# High_Voltage_H-Bridge.net
KiCad netlist of a schematic drawn in Altium Designer
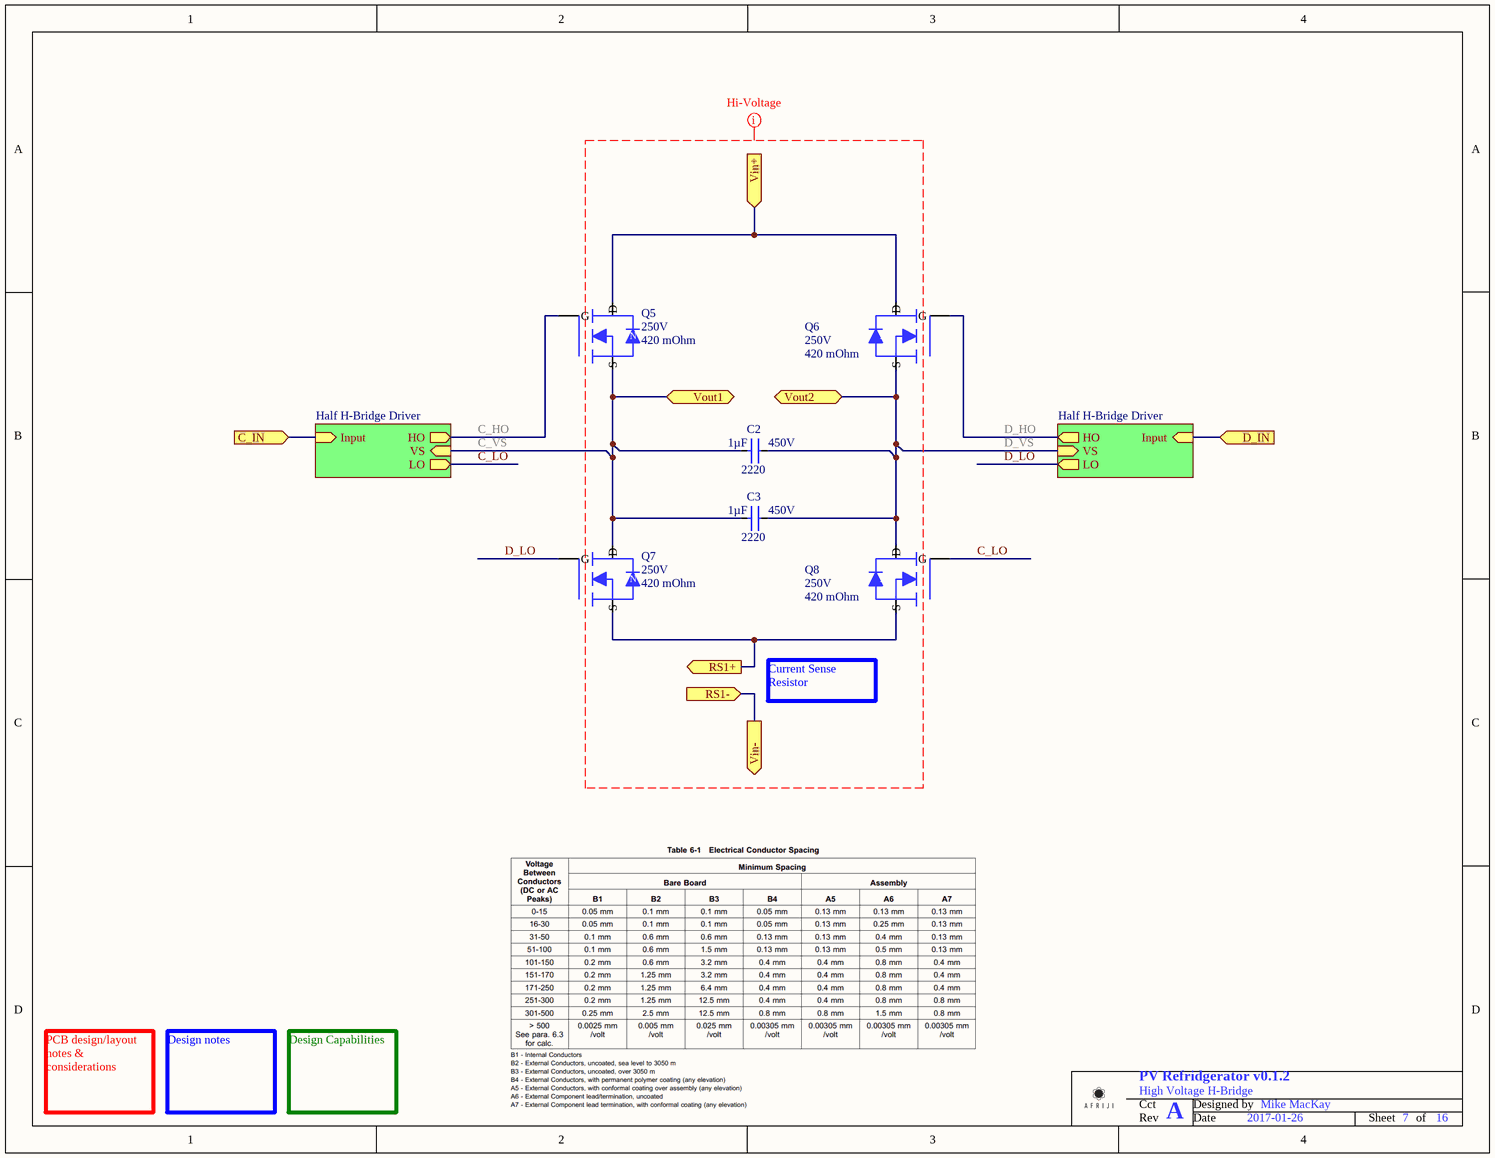
[diagram p0: High Voltage H-Bridge.SchDoc]

(export (version "E")
  (design (tool "Eeschema 10.0.6"))
  (components
    (comp (ref "C2")
      (value "1uF 2220 450V")
      (footprint "C2220 - Ceramic")
      (fields
        (field (name "MANUFACTURER") "TDK Corporation")
        (field (name "MANUFACTURER PART NUMBER") "CGA9P4X7T2W105M250KE")
        (field (name "TOLERANCE") "±20%")
        (field (name "CAPACITANCE") "1µF")
        (field (name "VOLTAGE - RATED") "450V")
        (field (name "PACKAGE / CASE") "2220")
      )
      (libsource (lib "Local Library") (part "1uF 2220 450V"))
    )
    (comp (ref "C3")
      (value "1uF 2220 450V")
      (footprint "C2220 - Ceramic")
      (fields
        (field (name "MANUFACTURER") "TDK Corporation")
        (field (name "MANUFACTURER PART NUMBER") "CGA9P4X7T2W105M250KE")
        (field (name "TOLERANCE") "±20%")
        (field (name "CAPACITANCE") "1µF")
        (field (name "VOLTAGE - RATED") "450V")
        (field (name "PACKAGE / CASE") "2220")
      )
      (libsource (lib "Local Library") (part "1uF 2220 450V"))
    )
    (comp (ref "Q5")
      (value "N-MOSFET 420mR 250V")
      (footprint "DPAK")
      (fields
        (field (name "MANUFACTURER") "Fairchild/ON Semiconductor")
        (field (name "MANUFACTURER PART NUMBER") "FQD9N25TM")
        (field (name "DRAIN TO SOURCE VOLTAGE (VDSS)") "250V")
        (field (name "RDS ON (MAX) @ ID, VGS") "420 mOhm")
      )
      (libsource (lib "Local Library") (part "N-MOSFET 420mR 250V"))
    )
    (comp (ref "Q6")
      (value "N-MOSFET 420mR 250V")
      (footprint "DPAK")
      (fields
        (field (name "MANUFACTURER") "Fairchild/ON Semiconductor")
        (field (name "MANUFACTURER PART NUMBER") "FQD9N25TM")
        (field (name "DRAIN TO SOURCE VOLTAGE (VDSS)") "250V")
        (field (name "RDS ON (MAX) @ ID, VGS") "420 mOhm")
      )
      (libsource (lib "Local Library") (part "N-MOSFET 420mR 250V"))
    )
    (comp (ref "Q7")
      (value "N-MOSFET 420mR 250V")
      (footprint "DPAK")
      (fields
        (field (name "MANUFACTURER") "Fairchild/ON Semiconductor")
        (field (name "MANUFACTURER PART NUMBER") "FQD9N25TM")
        (field (name "DRAIN TO SOURCE VOLTAGE (VDSS)") "250V")
        (field (name "RDS ON (MAX) @ ID, VGS") "420 mOhm")
      )
      (libsource (lib "Local Library") (part "N-MOSFET 420mR 250V"))
    )
    (comp (ref "Q8")
      (value "N-MOSFET 420mR 250V")
      (footprint "DPAK")
      (fields
        (field (name "MANUFACTURER") "Fairchild/ON Semiconductor")
        (field (name "MANUFACTURER PART NUMBER") "FQD9N25TM")
        (field (name "DRAIN TO SOURCE VOLTAGE (VDSS)") "250V")
        (field (name "RDS ON (MAX) @ ID, VGS") "420 mOhm")
      )
      (libsource (lib "Local Library") (part "N-MOSFET 420mR 250V"))
    )
  )
  (nets
    (net (code "1") (name "/C_HO") (class "Default")
      (node (ref "Q5") (pin "1") (pinfunction "G_1") (pintype "passive"))
    )
    (net (code "3") (name "/C_LO") (class "Default")
      (node (ref "Q8") (pin "1") (pinfunction "G_1") (pintype "passive"))
    )
    (net (code "4") (name "/C_VS") (class "Default")
      (node (ref "C2") (pin "1") (pinfunction "1_1") (pintype "passive"))
      (node (ref "C3") (pin "1") (pinfunction "1_1") (pintype "passive"))
      (node (ref "Q5") (pin "3") (pinfunction "S_3") (pintype "passive"))
      (node (ref "Q7") (pin "2") (pinfunction "D_2") (pintype "passive"))
    )
    (net (code "5") (name "/D_HO") (class "Default")
      (node (ref "Q6") (pin "1") (pinfunction "G_1") (pintype "passive"))
    )
    (net (code "7") (name "/D_LO") (class "Default")
      (node (ref "Q7") (pin "1") (pinfunction "G_1") (pintype "passive"))
    )
    (net (code "8") (name "/D_VS") (class "Default")
      (node (ref "C2") (pin "2") (pinfunction "2_2") (pintype "passive"))
      (node (ref "C3") (pin "2") (pinfunction "2_2") (pintype "passive"))
      (node (ref "Q6") (pin "3") (pinfunction "S_3") (pintype "passive"))
      (node (ref "Q8") (pin "2") (pinfunction "D_2") (pintype "passive"))
    )
    (net (code "9") (name "/RS1+") (class "Default")
      (node (ref "Q7") (pin "3") (pinfunction "S_3") (pintype "passive"))
      (node (ref "Q8") (pin "3") (pinfunction "S_3") (pintype "passive"))
    )
    (net (code "11") (name "/Vin+") (class "Default")
      (node (ref "Q5") (pin "2") (pinfunction "D_2") (pintype "passive"))
      (node (ref "Q6") (pin "2") (pinfunction "D_2") (pintype "passive"))
    )
  )
)
